# IO_Management.net
KiCad netlist of a schematic drawn in Altium Designer
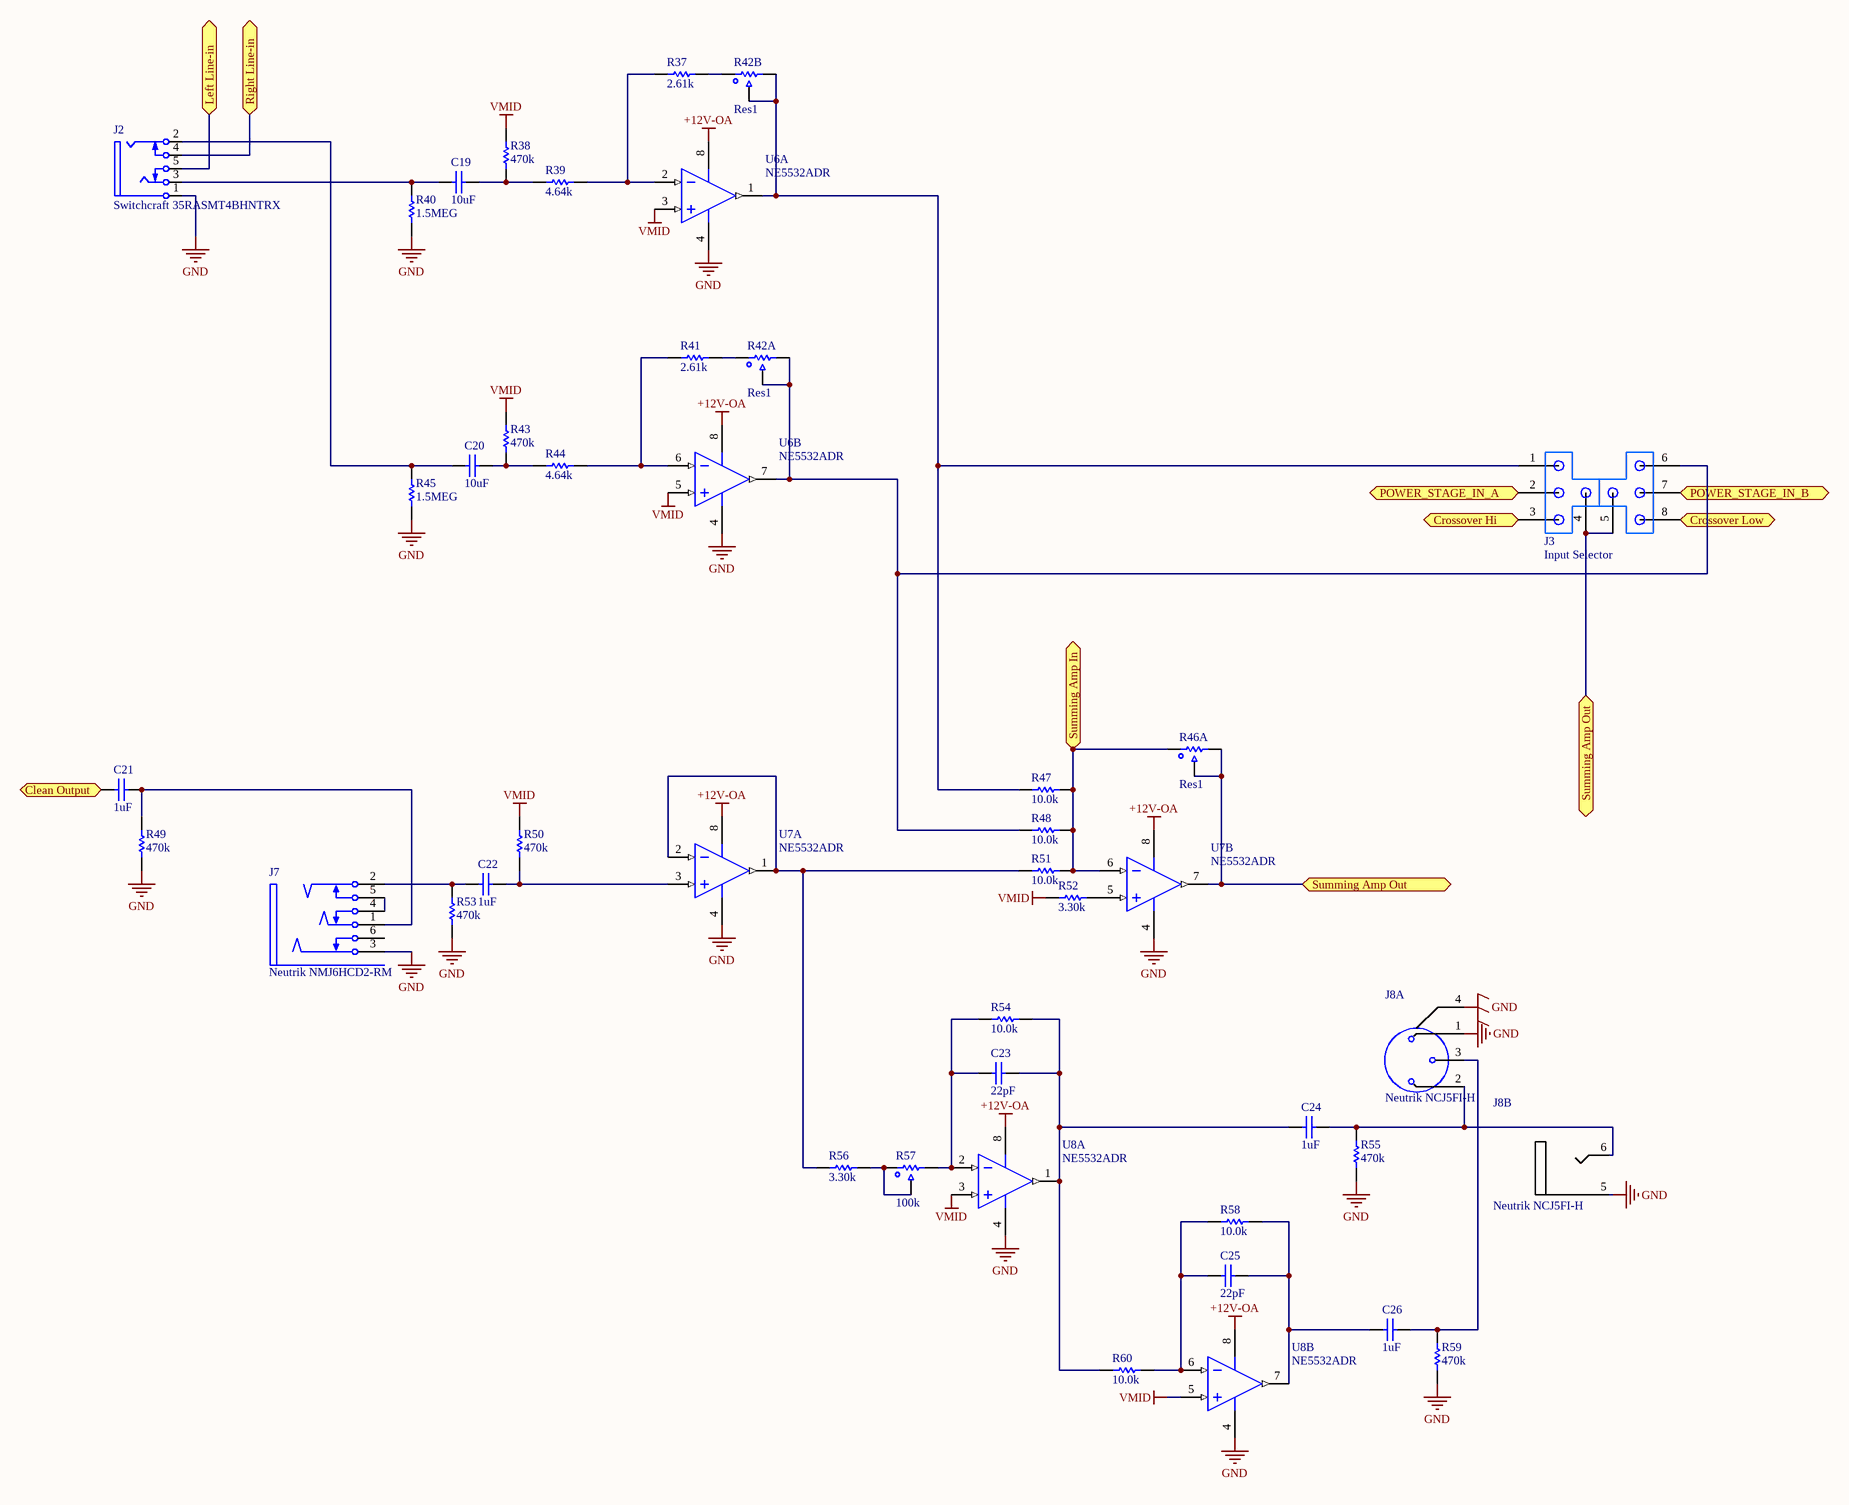
[diagram p0: IO Management.SchDoc]

(export (version "E")
  (design (tool "Eeschema 10.0.6"))
  (components
    (comp (ref "C19")
      (value "10uF")
      (footprint "PCB-5c5sxu4lzqbcrp2k6kwf-1")
      (description "Cap Film 10uF 63V PET 5% (26.5 X 8.5 X 17mm) Radial Wound 22.5mm 105C Automotive Bulk")
      (fields (field (name "MANUFACTURER PART NUMBER") "60DN51005030J") (field (name "MANUFACTURER") "Kemet"))
      (libsource (lib "CommunityVault") (part "SYM-f13b3967d5202efc-1"))
    )
    (comp (ref "C20")
      (value "10uF")
      (footprint "PCB-5c5sxu4lzqbcrp2k6kwf-1")
      (description "Cap Film 10uF 63V PET 5% (26.5 X 8.5 X 17mm) Radial Wound 22.5mm 105C Automotive Bulk")
      (fields (field (name "MANUFACTURER PART NUMBER") "60DN51005030J") (field (name "MANUFACTURER") "Kemet"))
      (libsource (lib "CommunityVault") (part "SYM-f13b3967d5202efc-1"))
    )
    (comp (ref "C21")
      (value "1uF")
      (footprint "PCB-2wbb7ys4jm9z9dflo2i2-1")
      (description "B32529 Series 63 V 1 uF Radial LS=5 mm Stacked Metallized PET Film Capacitor")
      (fields (field (name "MANUFACTURER PART NUMBER") "B32529C105J289") (field (name "MANUFACTURER") "TDK"))
      (libsource (lib "CommunityVault") (part "CMP-85fe4cf7e9a75a39-2"))
    )
    (comp (ref "C22")
      (value "1uF")
      (footprint "PCB-2wbb7ys4jm9z9dflo2i2-1")
      (description "B32529 Series 63 V 1 uF Radial LS=5 mm Stacked Metallized PET Film Capacitor")
      (fields (field (name "MANUFACTURER PART NUMBER") "B32529C105J289") (field (name "MANUFACTURER") "TDK"))
      (libsource (lib "CommunityVault") (part "CMP-85fe4cf7e9a75a39-2"))
    )
    (comp (ref "C23")
      (value "22pF")
      (footprint "PCB-o7p1koxmr9wqz41gh50t-1")
      (description "CL10 Series 22 pF 50V ±5 % Tolerance C0G SMT Multilayer Ceramic Capacitor")
      (fields
        (field (name "MANUFACTURER") "Samsung")
        (field (name "MANUFACTURER PART NUMBER") "CL10C220JB8NNNC")
      )
      (libsource (lib "CommunityVault") (part "SYM-5839914dedd787fe-1"))
    )
    (comp (ref "C24")
      (value "1uF")
      (footprint "PCB-2wbb7ys4jm9z9dflo2i2-1")
      (description "B32529 Series 63 V 1 uF Radial LS=5 mm Stacked Metallized PET Film Capacitor")
      (fields (field (name "MANUFACTURER PART NUMBER") "B32529C105J289") (field (name "MANUFACTURER") "TDK"))
      (libsource (lib "CommunityVault") (part "CMP-85fe4cf7e9a75a39-2"))
    )
    (comp (ref "C25")
      (value "22pF")
      (footprint "PCB-o7p1koxmr9wqz41gh50t-1")
      (description "CL10 Series 22 pF 50V ±5 % Tolerance C0G SMT Multilayer Ceramic Capacitor")
      (fields
        (field (name "MANUFACTURER") "Samsung")
        (field (name "MANUFACTURER PART NUMBER") "CL10C220JB8NNNC")
      )
      (libsource (lib "CommunityVault") (part "SYM-5839914dedd787fe-1"))
    )
    (comp (ref "C26")
      (value "1uF")
      (footprint "PCB-2wbb7ys4jm9z9dflo2i2-1")
      (description "B32529 Series 63 V 1 uF Radial LS=5 mm Stacked Metallized PET Film Capacitor")
      (fields (field (name "MANUFACTURER PART NUMBER") "B32529C105J289") (field (name "MANUFACTURER") "TDK"))
      (libsource (lib "CommunityVault") (part "CMP-85fe4cf7e9a75a39-2"))
    )
    (comp (ref "J2")
      (value "Switchcraft 35RASMT4BHNTRX")
      (footprint "SWIT-35RASMT4BHNTRX_V")
      (description "Female 3.5 mm Phone Jack, 5 Position, Height 5 mm, RoHS, Tape and Reel")
      (fields (field (name "MANUFACTURER PART NUMBER") "35RASMT4BHNTRX"))
      (libsource (lib "CommunityVault") (part "CMP-329442-8"))
    )
    (comp (ref "J3")
      (value "Input Selector")
      (footprint "PCB-r6lzv2511lj5epnn9hpr-1")
      (description "3 way stereo H-shaped pin header jumper 2.54mm")
      (libsource (lib "CommunityVault") (part "CMP-fydh8mqcn19uwpn0klog-2"))
    )
    (comp (ref "J7")
      (value "Neutrik NMJ6HCD2-RM")
      (footprint "PCB-3345220-1")
      (description "Phone Connectors 1/4\" STERO JCK SWTCH FULL TRD NSE PC HORZ")
      (fields (field (name "MANUFACTURER") "Neutrik") (field (name "MANUFACTURER PART NUMBER") "NMJ6HCD2-RM"))
      (libsource (lib "CommunityVault") (part "CMP-3345220-6"))
    )
    (comp (ref "J8")
      (value "Neutrik NCJ5FI-H")
      (footprint "PCB-kqs2tegzu26oi3jl7i0a-1")
      (description "Neutrik NCJ5FI-H Combo 3-Pin XLRF / 1/4 Inch Mono Horizontal PCB Mount")
      (fields (field (name "MANUFACTURER PART NUMBER") "NCJ5FI-H") (field (name "MANUFACTURER") "Neutrik"))
      (libsource (lib "CommunityVault") (part "CMP-d6ad1fac6a3f096a-1"))
    )
    (comp (ref "R37")
      (value "2.61k")
      (footprint "PCB-2fy4x9bysi6rpexrr8fu-1")
      (description "Res Thin Film 0603 2.61K Ohm 0.1% 1/10W ±25ppm/°C Molded SMD Paper T/R")
      (fields
        (field (name "MANUFACTURER") "Vishay")
        (field (name "MANUFACTURER PART NUMBER") "MCT06030D2611BP100")
      )
      (libsource (lib "CommunityVault") (part "SYM-9c6957e4a20743ae-1"))
    )
    (comp (ref "R38")
      (value "470k")
      (footprint "RESC1609X55X28LL05T18")
      (description "Res Thin Film 0603 470K Ohm 0.1% 1/10W ±25ppm/°C Molded SMD SMD Paper T/R")
      (fields (field (name "MANUFACTURER PART NUMBER") "MCT06030D4703BP100"))
      (libsource (lib "CommunityVault") (part "CMP-f7e03fd772d42827-1"))
    )
    (comp (ref "R39")
      (value "4.64k")
      (footprint "RESC1609X55X28LL05T18")
      (description "Res Thin Film 0603 4.64K Ohm 0.1% 1/10W ±25ppm/°C Molded SMD SMD Paper T/R")
      (fields (field (name "MANUFACTURER PART NUMBER") "MCT06030D4641BP100"))
      (libsource (lib "CommunityVault") (part "SYM-ae07668bb89171c0-1"))
    )
    (comp (ref "R40")
      (value "1.5MEG")
      (footprint "RESC1608X55X30LL15T15")
      (description "Thick Film Resistors - SMD 0603 1.5Mohms 1% Tol")
      (fields
        (field (name "MANUFACTURER PART NUMBER") "ERJ-3EKF1504V")
        (field (name "MANUFACTURER") "Panasonic")
      )
      (libsource (lib "CommunityVault") (part "CMP-3681775-2"))
    )
    (comp (ref "R41")
      (value "2.61k")
      (footprint "PCB-2fy4x9bysi6rpexrr8fu-1")
      (description "Res Thin Film 0603 2.61K Ohm 0.1% 1/10W ±25ppm/°C Molded SMD Paper T/R")
      (fields
        (field (name "MANUFACTURER") "Vishay")
        (field (name "MANUFACTURER PART NUMBER") "MCT06030D2611BP100")
      )
      (libsource (lib "CommunityVault") (part "CMP-9c6957e4a20743ae-1"))
    )
    (comp (ref "R42")
      (value "Res1")
      (footprint "PCB-3c7eria7znpasna51pjn-1")
      (description "Panel Control - 9mm-St-Carbon")
      (libsource (lib "CommunityVault") (part "CMP-f1923a8ba4e42e55-1"))
    )
    (comp (ref "R43")
      (value "470k")
      (footprint "RESC1609X55X28LL05T18")
      (description "Res Thin Film 0603 470K Ohm 0.1% 1/10W ±25ppm/°C Molded SMD SMD Paper T/R")
      (fields (field (name "MANUFACTURER PART NUMBER") "MCT06030D4703BP100"))
      (libsource (lib "CommunityVault") (part "SYM-f7e03fd772d42827-1"))
    )
    (comp (ref "R44")
      (value "4.64k")
      (footprint "RESC1609X55X28LL05T18")
      (description "Res Thin Film 0603 4.64K Ohm 0.1% 1/10W ±25ppm/°C Molded SMD SMD Paper T/R")
      (fields (field (name "MANUFACTURER PART NUMBER") "MCT06030D4641BP100"))
      (libsource (lib "CommunityVault") (part "SYM-ae07668bb89171c0-1"))
    )
    (comp (ref "R45")
      (value "1.5MEG")
      (footprint "RESC1608X55X30LL15T15")
      (description "Thick Film Resistors - SMD 0603 1.5Mohms 1% Tol")
      (fields
        (field (name "MANUFACTURER PART NUMBER") "ERJ-3EKF1504V")
        (field (name "MANUFACTURER") "Panasonic")
      )
      (libsource (lib "CommunityVault") (part "CMP-3681775-2"))
    )
    (comp (ref "R46")
      (value "Res1")
      (footprint "PCB-3c7eria7znpasna51pjn-1")
      (description "Panel Control - 9mm-St-Carbon")
      (libsource (lib "CommunityVault") (part "CMP-f1923a8ba4e42e55-1"))
    )
    (comp (ref "R47")
      (value "10.0k")
      (footprint "RESC1609X55X28LL05T18")
      (description "Precision Thin Film Smnt Resistor 0603 Case 10kOhm +/-0.1% 0.1W +/-25ppm/degC")
      (fields
        (field (name "MANUFACTURER") "Vishay")
        (field (name "MANUFACTURER PART NUMBER") "MCT06030D1002BP100")
      )
      (libsource (lib "CommunityVault") (part "SYM-893e42b9f3a056f9-1"))
    )
    (comp (ref "R48")
      (value "10.0k")
      (footprint "RESC1609X55X28LL05T18")
      (description "Precision Thin Film Smnt Resistor 0603 Case 10kOhm +/-0.1% 0.1W +/-25ppm/degC")
      (fields
        (field (name "MANUFACTURER") "Vishay")
        (field (name "MANUFACTURER PART NUMBER") "MCT06030D1002BP100")
      )
      (libsource (lib "CommunityVault") (part "SYM-893e42b9f3a056f9-1"))
    )
    (comp (ref "R49")
      (value "470k")
      (footprint "RESC1609X55X28LL05T18")
      (description "Res Thin Film 0603 470K Ohm 0.1% 1/10W ±25ppm/°C Molded SMD SMD Paper T/R")
      (fields (field (name "MANUFACTURER PART NUMBER") "MCT06030D4703BP100"))
      (libsource (lib "CommunityVault") (part "SYM-f7e03fd772d42827-1"))
    )
    (comp (ref "R50")
      (value "470k")
      (footprint "RESC1609X55X28LL05T18")
      (description "Res Thin Film 0603 470K Ohm 0.1% 1/10W ±25ppm/°C Molded SMD SMD Paper T/R")
      (fields (field (name "MANUFACTURER PART NUMBER") "MCT06030D4703BP100"))
      (libsource (lib "CommunityVault") (part "SYM-f7e03fd772d42827-1"))
    )
    (comp (ref "R51")
      (value "10.0k")
      (footprint "RESC1609X55X28LL05T18")
      (description "Precision Thin Film Smnt Resistor 0603 Case 10kOhm +/-0.1% 0.1W +/-25ppm/degC")
      (fields
        (field (name "MANUFACTURER") "Vishay")
        (field (name "MANUFACTURER PART NUMBER") "MCT06030D1002BP100")
      )
      (libsource (lib "CommunityVault") (part "SYM-893e42b9f3a056f9-1"))
    )
    (comp (ref "R52")
      (value "3.30k")
      (footprint "RESC1609X55X28LL05T18")
      (description "Precision Thin Film Smnt Resistor 0603 Case 3.3kOhm +/-0.1% 0.1W +/-25ppm/C")
      (fields
        (field (name "MANUFACTURER") "Vishay")
        (field (name "MANUFACTURER PART NUMBER") "MCT06030D3301BP100")
      )
      (libsource (lib "CommunityVault") (part "SYM-182ad3b0fdf8c7ed-1"))
    )
    (comp (ref "R53")
      (value "470k")
      (footprint "RESC1609X55X28LL05T18")
      (description "Res Thin Film 0603 470K Ohm 0.1% 1/10W ±25ppm/°C Molded SMD SMD Paper T/R")
      (fields (field (name "MANUFACTURER PART NUMBER") "MCT06030D4703BP100"))
      (libsource (lib "CommunityVault") (part "SYM-f7e03fd772d42827-1"))
    )
    (comp (ref "R54")
      (value "10.0k")
      (footprint "RESC1609X55X28LL05T18")
      (description "Precision Thin Film Smnt Resistor 0603 Case 10kOhm +/-0.1% 0.1W +/-25ppm/degC")
      (fields
        (field (name "MANUFACTURER") "Vishay")
        (field (name "MANUFACTURER PART NUMBER") "MCT06030D1002BP100")
      )
      (libsource (lib "CommunityVault") (part "SYM-893e42b9f3a056f9-1"))
    )
    (comp (ref "R55")
      (value "470k")
      (footprint "RESC1609X55X28LL05T18")
      (description "Res Thin Film 0603 470K Ohm 0.1% 1/10W ±25ppm/°C Molded SMD SMD Paper T/R")
      (fields (field (name "MANUFACTURER PART NUMBER") "MCT06030D4703BP100"))
      (libsource (lib "CommunityVault") (part "SYM-f7e03fd772d42827-1"))
    )
    (comp (ref "R56")
      (value "3.30k")
      (footprint "RESC1609X55X28LL05T18")
      (description "Precision Thin Film Smnt Resistor 0603 Case 3.3kOhm +/-0.1% 0.1W +/-25ppm/C")
      (fields
        (field (name "MANUFACTURER") "Vishay")
        (field (name "MANUFACTURER PART NUMBER") "MCT06030D3301BP100")
      )
      (libsource (lib "CommunityVault") (part "SYM-182ad3b0fdf8c7ed-1"))
    )
    (comp (ref "R57")
      (value "100k")
      (footprint "PCB-3c7eria7znpasna51pjn-1")
      (description "Pot 100k Ohm 1/20w Carbon Linear")
      (fields (field (name "MANUFACTURER PART NUMBER") "PTD901-2015F-B104"))
      (libsource (lib "CommunityVault") (part "SYM-ada7643275df7260-1"))
    )
    (comp (ref "R58")
      (value "10.0k")
      (footprint "RESC1609X55X28LL05T18")
      (description "Precision Thin Film Smnt Resistor 0603 Case 10kOhm +/-0.1% 0.1W +/-25ppm/degC")
      (fields
        (field (name "MANUFACTURER") "Vishay")
        (field (name "MANUFACTURER PART NUMBER") "MCT06030D1002BP100")
      )
      (libsource (lib "CommunityVault") (part "SYM-893e42b9f3a056f9-1"))
    )
    (comp (ref "R59")
      (value "470k")
      (footprint "RESC1609X55X28LL05T18")
      (description "Res Thin Film 0603 470K Ohm 0.1% 1/10W ±25ppm/°C Molded SMD SMD Paper T/R")
      (fields (field (name "MANUFACTURER PART NUMBER") "MCT06030D4703BP100"))
      (libsource (lib "CommunityVault") (part "SYM-f7e03fd772d42827-1"))
    )
    (comp (ref "R60")
      (value "10.0k")
      (footprint "RESC1609X55X28LL05T18")
      (description "Precision Thin Film Smnt Resistor 0603 Case 10kOhm +/-0.1% 0.1W +/-25ppm/degC")
      (fields
        (field (name "MANUFACTURER") "Vishay")
        (field (name "MANUFACTURER PART NUMBER") "MCT06030D1002BP100")
      )
      (libsource (lib "CommunityVault") (part "SYM-893e42b9f3a056f9-1"))
    )
    (comp (ref "U6")
      (value "NE5532ADR")
      (footprint "TI-D8_L")
      (libsource (lib "CommunityVault") (part "CMP-13597030-2"))
    )
    (comp (ref "U7")
      (value "NE5532ADR")
      (footprint "TI-D8_L")
      (libsource (lib "CommunityVault") (part "CMP-13597030-2"))
    )
    (comp (ref "U8")
      (value "NE5532ADR")
      (footprint "TI-D8_L")
      (libsource (lib "CommunityVault") (part "CMP-13597030-2"))
    )
  )
  (nets
    (net (code "1") (name "+12V-OA") (class "Default")
      (node (ref "U6") (pin "8") (pinfunction "VCC+_8") (pintype "power_in"))
      (node (ref "U7") (pin "8") (pinfunction "VCC+_8") (pintype "power_in"))
      (node (ref "U8") (pin "8") (pinfunction "VCC+_8") (pintype "power_in"))
    )
    (net (code "2") (name "/Clean Output") (class "Default")
      (node (ref "C21") (pin "1") (pinfunction "1_1") (pintype "passive"))
    )
    (net (code "3") (name "/Crossover Hi") (class "Default")
      (node (ref "J3") (pin "3") (pinfunction "3_3") (pintype "passive"))
    )
    (net (code "4") (name "/Crossover Low") (class "Default")
      (node (ref "J3") (pin "8") (pinfunction "8_8") (pintype "passive"))
    )
    (net (code "5") (name "/Left Line-in") (class "Default")
      (node (ref "J2") (pin "5") (pinfunction "5_5") (pintype "passive"))
    )
    (net (code "6") (name "/POWER_STAGE_IN_A") (class "Default")
      (node (ref "J3") (pin "2") (pinfunction "2_2") (pintype "passive"))
    )
    (net (code "7") (name "/POWER_STAGE_IN_B") (class "Default")
      (node (ref "J3") (pin "7") (pinfunction "7_7") (pintype "passive"))
    )
    (net (code "8") (name "/Right Line-in") (class "Default")
      (node (ref "J2") (pin "4") (pinfunction "4_4") (pintype "passive"))
    )
    (net (code "9") (name "/Summing Amp In") (class "Default")
      (node (ref "R46") (pin "R1_1") (pinfunction "R1_1_R1_1") (pintype "passive"))
      (node (ref "R47") (pin "2") (pinfunction "2_2") (pintype "passive"))
      (node (ref "R48") (pin "2") (pinfunction "2_2") (pintype "passive"))
      (node (ref "R51") (pin "2") (pinfunction "2_2") (pintype "passive"))
      (node (ref "U7") (pin "6") (pinfunction "IN2-_6") (pintype "input"))
    )
    (net (code "10") (name "/Summing Amp Out") (class "Default")
      (node (ref "J3") (pin "4") (pinfunction "4_4") (pintype "passive"))
      (node (ref "J3") (pin "5") (pinfunction "5_5") (pintype "passive"))
      (node (ref "R46") (pin "R1_2") (pinfunction "R1_2_R1_2") (pintype "passive"))
      (node (ref "R46") (pin "R1_3") (pinfunction "R1_3_R1_3") (pintype "passive"))
      (node (ref "U7") (pin "7") (pinfunction "OUT2_7") (pintype "output"))
    )
    (net (code "11") (name "GND") (class "Default")
      (node (ref "J2") (pin "1") (pinfunction "1_1") (pintype "passive"))
      (node (ref "J7") (pin "3") (pinfunction "3_3") (pintype "passive"))
      (node (ref "J8") (pin "1") (pinfunction "1_1") (pintype "passive"))
      (node (ref "J8") (pin "4") (pinfunction "G_4") (pintype "passive"))
      (node (ref "J8") (pin "5") (pinfunction "S_5") (pintype "passive"))
      (node (ref "R40") (pin "1") (pinfunction "1_1") (pintype "passive"))
      (node (ref "R45") (pin "1") (pinfunction "1_1") (pintype "passive"))
      (node (ref "R49") (pin "1") (pinfunction "1_1") (pintype "passive"))
      (node (ref "R53") (pin "1") (pinfunction "1_1") (pintype "passive"))
      (node (ref "R55") (pin "1") (pinfunction "1_1") (pintype "passive"))
      (node (ref "R59") (pin "1") (pinfunction "1_1") (pintype "passive"))
      (node (ref "U6") (pin "4") (pinfunction "VCC-_4") (pintype "power_in"))
      (node (ref "U7") (pin "4") (pinfunction "VCC-_4") (pintype "power_in"))
      (node (ref "U8") (pin "4") (pinfunction "VCC-_4") (pintype "power_in"))
    )
    (net (code "12") (name "Net-(C19-Pad1)") (class "Default")
      (node (ref "C19") (pin "1") (pinfunction "1_1") (pintype "passive"))
      (node (ref "J2") (pin "3") (pinfunction "3_3") (pintype "passive"))
      (node (ref "R40") (pin "2") (pinfunction "2_2") (pintype "passive"))
    )
    (net (code "13") (name "Net-(C19-Pad2)") (class "Default")
      (node (ref "C19") (pin "2") (pinfunction "2_2") (pintype "passive"))
      (node (ref "R38") (pin "1") (pinfunction "1_1") (pintype "passive"))
      (node (ref "R39") (pin "1") (pinfunction "1_1") (pintype "passive"))
    )
    (net (code "14") (name "Net-(C20-Pad1)") (class "Default")
      (node (ref "C20") (pin "1") (pinfunction "1_1") (pintype "passive"))
      (node (ref "J2") (pin "2") (pinfunction "2_2") (pintype "passive"))
      (node (ref "R45") (pin "2") (pinfunction "2_2") (pintype "passive"))
    )
    (net (code "15") (name "Net-(C20-Pad2)") (class "Default")
      (node (ref "C20") (pin "2") (pinfunction "2_2") (pintype "passive"))
      (node (ref "R43") (pin "1") (pinfunction "1_1") (pintype "passive"))
      (node (ref "R44") (pin "1") (pinfunction "1_1") (pintype "passive"))
    )
    (net (code "16") (name "Net-(C21-Pad2)") (class "Default")
      (node (ref "C21") (pin "2") (pinfunction "2_2") (pintype "passive"))
      (node (ref "J7") (pin "1") (pinfunction "1_1") (pintype "passive"))
      (node (ref "R49") (pin "2") (pinfunction "2_2") (pintype "passive"))
    )
    (net (code "17") (name "Net-(C22-Pad1)") (class "Default")
      (node (ref "C22") (pin "1") (pinfunction "1_1") (pintype "passive"))
      (node (ref "J7") (pin "2") (pinfunction "2_2") (pintype "passive"))
      (node (ref "R53") (pin "2") (pinfunction "2_2") (pintype "passive"))
    )
    (net (code "18") (name "Net-(C26-Pad2)") (class "Default")
      (node (ref "C26") (pin "2") (pinfunction "2_2") (pintype "passive"))
      (node (ref "J8") (pin "3") (pinfunction "3_3") (pintype "passive"))
      (node (ref "R59") (pin "2") (pinfunction "2_2") (pintype "passive"))
    )
    (net (code "19") (name "Net-(J7-Pad4)") (class "Default")
      (node (ref "J7") (pin "4") (pinfunction "4_4") (pintype "passive"))
      (node (ref "J7") (pin "5") (pinfunction "5_5") (pintype "passive"))
    )
    (net (code "20") (name "Net-(J8B-T)") (class "Default")
      (node (ref "C24") (pin "2") (pinfunction "2_2") (pintype "passive"))
      (node (ref "J8") (pin "2") (pinfunction "2_2") (pintype "passive"))
      (node (ref "J8") (pin "6") (pinfunction "T_6") (pintype "passive"))
      (node (ref "R55") (pin "2") (pinfunction "2_2") (pintype "passive"))
    )
    (net (code "21") (name "Net-(R37-Pad2)") (class "Default")
      (node (ref "R37") (pin "2") (pinfunction "2_2") (pintype "passive"))
      (node (ref "R42") (pin "R2_1") (pinfunction "R2_1_R2_1") (pintype "passive"))
    )
    (net (code "22") (name "Net-(R41-Pad2)") (class "Default")
      (node (ref "R41") (pin "2") (pinfunction "2_2") (pintype "passive"))
      (node (ref "R42") (pin "R1_1") (pinfunction "R1_1_R1_1") (pintype "passive"))
    )
    (net (code "23") (name "Net-(R56-Pad2)") (class "Default")
      (node (ref "R56") (pin "2") (pinfunction "2_2") (pintype "passive"))
      (node (ref "R57") (pin "1") (pinfunction "1_1") (pintype "passive"))
      (node (ref "R57") (pin "2") (pinfunction "2_2") (pintype "passive"))
    )
    (net (code "24") (name "Net-(U6A-IN1-)") (class "Default")
      (node (ref "R37") (pin "1") (pinfunction "1_1") (pintype "passive"))
      (node (ref "R39") (pin "2") (pinfunction "2_2") (pintype "passive"))
      (node (ref "U6") (pin "2") (pinfunction "IN1-_2") (pintype "input"))
    )
    (net (code "25") (name "Net-(U6A-OUT1)") (class "Default")
      (node (ref "J3") (pin "1") (pinfunction "1_1") (pintype "passive"))
      (node (ref "R42") (pin "R2_2") (pinfunction "R2_2_R2_2") (pintype "passive"))
      (node (ref "R42") (pin "R2_3") (pinfunction "R2_3_R2_3") (pintype "passive"))
      (node (ref "R47") (pin "1") (pinfunction "1_1") (pintype "passive"))
      (node (ref "U6") (pin "1") (pinfunction "OUT1_1") (pintype "output"))
    )
    (net (code "26") (name "Net-(U6B-IN2-)") (class "Default")
      (node (ref "R41") (pin "1") (pinfunction "1_1") (pintype "passive"))
      (node (ref "R44") (pin "2") (pinfunction "2_2") (pintype "passive"))
      (node (ref "U6") (pin "6") (pinfunction "IN2-_6") (pintype "input"))
    )
    (net (code "27") (name "Net-(U6B-OUT2)") (class "Default")
      (node (ref "J3") (pin "6") (pinfunction "6_6") (pintype "passive"))
      (node (ref "R42") (pin "R1_2") (pinfunction "R1_2_R1_2") (pintype "passive"))
      (node (ref "R42") (pin "R1_3") (pinfunction "R1_3_R1_3") (pintype "passive"))
      (node (ref "R48") (pin "1") (pinfunction "1_1") (pintype "passive"))
      (node (ref "U6") (pin "7") (pinfunction "OUT2_7") (pintype "output"))
    )
    (net (code "28") (name "Net-(U7A-IN1+)") (class "Default")
      (node (ref "C22") (pin "2") (pinfunction "2_2") (pintype "passive"))
      (node (ref "R50") (pin "1") (pinfunction "1_1") (pintype "passive"))
      (node (ref "U7") (pin "3") (pinfunction "IN1+_3") (pintype "input"))
    )
    (net (code "29") (name "Net-(U7A-IN1-)") (class "Default")
      (node (ref "R51") (pin "1") (pinfunction "1_1") (pintype "passive"))
      (node (ref "R56") (pin "1") (pinfunction "1_1") (pintype "passive"))
      (node (ref "U7") (pin "1") (pinfunction "OUT1_1") (pintype "output"))
      (node (ref "U7") (pin "2") (pinfunction "IN1-_2") (pintype "input"))
    )
    (net (code "30") (name "Net-(U7B-IN2+)") (class "Default")
      (node (ref "R52") (pin "2") (pinfunction "2_2") (pintype "passive"))
      (node (ref "U7") (pin "5") (pinfunction "IN2+_5") (pintype "input"))
    )
    (net (code "31") (name "Net-(U8A-IN1-)") (class "Default")
      (node (ref "C23") (pin "1") (pinfunction "1_1") (pintype "passive"))
      (node (ref "R54") (pin "1") (pinfunction "1_1") (pintype "passive"))
      (node (ref "R57") (pin "3") (pinfunction "3_3") (pintype "passive"))
      (node (ref "U8") (pin "2") (pinfunction "IN1-_2") (pintype "input"))
    )
    (net (code "32") (name "Net-(U8A-OUT1)") (class "Default")
      (node (ref "C23") (pin "2") (pinfunction "2_2") (pintype "passive"))
      (node (ref "C24") (pin "1") (pinfunction "1_1") (pintype "passive"))
      (node (ref "R54") (pin "2") (pinfunction "2_2") (pintype "passive"))
      (node (ref "R60") (pin "1") (pinfunction "1_1") (pintype "passive"))
      (node (ref "U8") (pin "1") (pinfunction "OUT1_1") (pintype "output"))
    )
    (net (code "33") (name "Net-(U8B-IN2-)") (class "Default")
      (node (ref "C25") (pin "1") (pinfunction "1_1") (pintype "passive"))
      (node (ref "R58") (pin "1") (pinfunction "1_1") (pintype "passive"))
      (node (ref "R60") (pin "2") (pinfunction "2_2") (pintype "passive"))
      (node (ref "U8") (pin "6") (pinfunction "IN2-_6") (pintype "input"))
    )
    (net (code "34") (name "Net-(U8B-OUT2)") (class "Default")
      (node (ref "C25") (pin "2") (pinfunction "2_2") (pintype "passive"))
      (node (ref "C26") (pin "1") (pinfunction "1_1") (pintype "passive"))
      (node (ref "R58") (pin "2") (pinfunction "2_2") (pintype "passive"))
      (node (ref "U8") (pin "7") (pinfunction "OUT2_7") (pintype "output"))
    )
    (net (code "35") (name "VMID") (class "Default")
      (node (ref "R38") (pin "2") (pinfunction "2_2") (pintype "passive"))
      (node (ref "R43") (pin "2") (pinfunction "2_2") (pintype "passive"))
      (node (ref "R50") (pin "2") (pinfunction "2_2") (pintype "passive"))
      (node (ref "R52") (pin "1") (pinfunction "1_1") (pintype "passive"))
      (node (ref "U6") (pin "3") (pinfunction "IN1+_3") (pintype "input"))
      (node (ref "U6") (pin "5") (pinfunction "IN2+_5") (pintype "input"))
      (node (ref "U8") (pin "3") (pinfunction "IN1+_3") (pintype "input"))
      (node (ref "U8") (pin "5") (pinfunction "IN2+_5") (pintype "input"))
    )
    (net (code "36") (name "unconnected-(J7-Pad6)") (class "Default")
      (node (ref "J7") (pin "6") (pinfunction "6_6") (pintype "passive"))
    )
  )
)
